# untitled.net
KiCad netlist of a schematic drawn in EAGLE
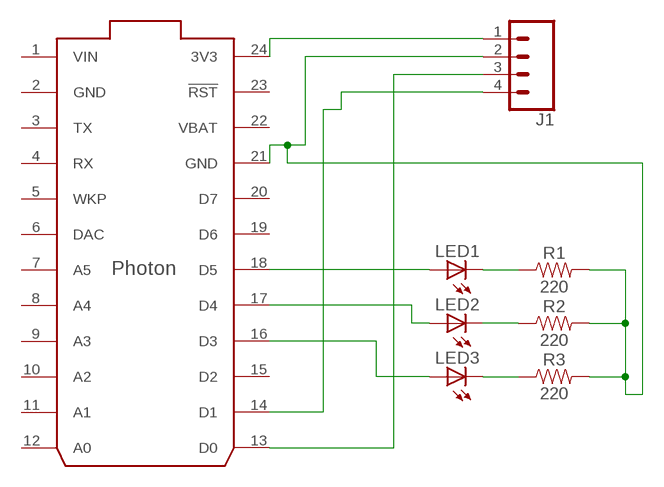
[diagram p0: schematic, sheet 1]

(export (version "E")
  (design (tool "Eeschema 10.0.6"))
  (components
    (comp (ref "J1")
      (value "CONN_04")
      (footprint "eagle-import:1X04")
      (libsource (lib "eagle-import") (part "CONN_04"))
    )
    (comp (ref "LED1")
      (value "LEDCHIP-LED0805")
      (footprint "eagle-import:CHIP-LED0805")
      (libsource (lib "eagle-import") (part "LEDCHIP-LED0805"))
    )
    (comp (ref "LED2")
      (value "LEDCHIP-LED0805")
      (footprint "eagle-import:CHIP-LED0805")
      (libsource (lib "eagle-import") (part "LEDCHIP-LED0805"))
    )
    (comp (ref "LED3")
      (value "LEDCHIP-LED0805")
      (footprint "eagle-import:CHIP-LED0805")
      (libsource (lib "eagle-import") (part "LEDCHIP-LED0805"))
    )
    (comp (ref "R1")
      (value "220")
      (footprint "eagle-import:0603")
      (libsource (lib "eagle-import") (part "220OHM-0603-1/10W-1%"))
    )
    (comp (ref "R2")
      (value "220")
      (footprint "eagle-import:0603")
      (libsource (lib "eagle-import") (part "220OHM-0603-1/10W-1%"))
    )
    (comp (ref "R3")
      (value "220")
      (footprint "eagle-import:0603")
      (libsource (lib "eagle-import") (part "220OHM-0603-1/10W-1%"))
    )
    (comp (ref "U$1")
      (value "PHOTON_WITH_HEADERS")
      (footprint "eagle-import:PHOTON")
      (libsource (lib "eagle-import") (part "PHOTON_WITH_HEADERS"))
    )
  )
  (nets
    (net (code "1") (name "/GND") (class "Default")
      (node (ref "U$1") (pin "2") (pinfunction "GND_2") (pintype "power_in"))
    )
    (net (code "2") (name "/VBAT") (class "Default")
      (node (ref "U$1") (pin "22") (pinfunction "VBAT_22") (pintype "power_in"))
    )
    (net (code "3") (name "/VIN") (class "Default")
      (node (ref "U$1") (pin "1") (pinfunction "VIN_1") (pintype "power_in"))
    )
    (net (code "4") (name "Net-(J1-Pad2)") (class "Default")
      (node (ref "J1") (pin "2") (pinfunction "2_2") (pintype "passive"))
      (node (ref "R1") (pin "2") (pinfunction "2_2") (pintype "passive"))
      (node (ref "R2") (pin "2") (pinfunction "2_2") (pintype "passive"))
      (node (ref "R3") (pin "2") (pinfunction "2_2") (pintype "passive"))
      (node (ref "U$1") (pin "21") (pinfunction "GND_21") (pintype "power_in"))
    )
    (net (code "5") (name "Net-(LED1-PadC)") (class "Default")
      (node (ref "LED1") (pin "C") (pinfunction "C_C") (pintype "passive"))
      (node (ref "R1") (pin "1") (pinfunction "1_1") (pintype "passive"))
    )
    (net (code "6") (name "Net-(LED2-PadC)") (class "Default")
      (node (ref "LED2") (pin "C") (pinfunction "C_C") (pintype "passive"))
      (node (ref "R2") (pin "1") (pinfunction "1_1") (pintype "passive"))
    )
    (net (code "7") (name "Net-(LED3-PadC)") (class "Default")
      (node (ref "LED3") (pin "C") (pinfunction "C_C") (pintype "passive"))
      (node (ref "R3") (pin "1") (pinfunction "1_1") (pintype "passive"))
    )
    (net (code "8") (name "Net-(U$1-3V3)") (class "Default")
      (node (ref "J1") (pin "1") (pinfunction "1_1") (pintype "passive"))
      (node (ref "U$1") (pin "24") (pinfunction "3V3_24") (pintype "power_in"))
    )
    (net (code "9") (name "Net-(U$1-D0)") (class "Default")
      (node (ref "J1") (pin "3") (pinfunction "3_3") (pintype "passive"))
      (node (ref "U$1") (pin "13") (pinfunction "D0_13") (pintype "bidirectional"))
    )
    (net (code "10") (name "Net-(U$1-D1)") (class "Default")
      (node (ref "J1") (pin "4") (pinfunction "4_4") (pintype "passive"))
      (node (ref "U$1") (pin "14") (pinfunction "D1_14") (pintype "bidirectional"))
    )
    (net (code "11") (name "Net-(U$1-D3)") (class "Default")
      (node (ref "LED3") (pin "A") (pinfunction "A_A") (pintype "passive"))
      (node (ref "U$1") (pin "16") (pinfunction "D3_16") (pintype "bidirectional"))
    )
    (net (code "12") (name "Net-(U$1-D4)") (class "Default")
      (node (ref "LED2") (pin "A") (pinfunction "A_A") (pintype "passive"))
      (node (ref "U$1") (pin "17") (pinfunction "D4_17") (pintype "bidirectional"))
    )
    (net (code "13") (name "Net-(U$1-D5)") (class "Default")
      (node (ref "LED1") (pin "A") (pinfunction "A_A") (pintype "passive"))
      (node (ref "U$1") (pin "18") (pinfunction "D5_18") (pintype "bidirectional"))
    )
    (net (code "14") (name "unconnected-(U$1-A0-Pad12)") (class "Default")
      (node (ref "U$1") (pin "12") (pinfunction "A0_12") (pintype "bidirectional"))
    )
    (net (code "15") (name "unconnected-(U$1-A1-Pad11)") (class "Default")
      (node (ref "U$1") (pin "11") (pinfunction "A1_11") (pintype "bidirectional"))
    )
    (net (code "16") (name "unconnected-(U$1-A2-Pad10)") (class "Default")
      (node (ref "U$1") (pin "10") (pinfunction "A2_10") (pintype "bidirectional"))
    )
    (net (code "17") (name "unconnected-(U$1-A3-Pad9)") (class "Default")
      (node (ref "U$1") (pin "9") (pinfunction "A3_9") (pintype "bidirectional"))
    )
    (net (code "18") (name "unconnected-(U$1-A4-Pad8)") (class "Default")
      (node (ref "U$1") (pin "8") (pinfunction "A4_8") (pintype "bidirectional"))
    )
    (net (code "19") (name "unconnected-(U$1-A5-Pad7)") (class "Default")
      (node (ref "U$1") (pin "7") (pinfunction "A5_7") (pintype "bidirectional"))
    )
    (net (code "20") (name "unconnected-(U$1-D2-Pad15)") (class "Default")
      (node (ref "U$1") (pin "15") (pinfunction "D2_15") (pintype "bidirectional"))
    )
    (net (code "21") (name "unconnected-(U$1-D6-Pad19)") (class "Default")
      (node (ref "U$1") (pin "19") (pinfunction "D6_19") (pintype "bidirectional"))
    )
    (net (code "22") (name "unconnected-(U$1-D7-Pad20)") (class "Default")
      (node (ref "U$1") (pin "20") (pinfunction "D7_20") (pintype "bidirectional"))
    )
    (net (code "23") (name "unconnected-(U$1-DAC-Pad6)") (class "Default")
      (node (ref "U$1") (pin "6") (pinfunction "DAC_6") (pintype "bidirectional"))
    )
    (net (code "24") (name "unconnected-(U$1-RX-Pad4)") (class "Default")
      (node (ref "U$1") (pin "4") (pinfunction "RX_4") (pintype "bidirectional"))
    )
    (net (code "25") (name "unconnected-(U$1-TX-Pad3)") (class "Default")
      (node (ref "U$1") (pin "3") (pinfunction "TX_3") (pintype "bidirectional"))
    )
    (net (code "26") (name "unconnected-(U$1-WKP-Pad5)") (class "Default")
      (node (ref "U$1") (pin "5") (pinfunction "WKP_5") (pintype "bidirectional"))
    )
    (net (code "27") (name "unconnected-(U$1-~{RST}-Pad23)") (class "Default")
      (node (ref "U$1") (pin "23") (pinfunction "~{RST}_23") (pintype "bidirectional"))
    )
  )
)
